# sc-7000z_supplyswitch.net
KiCad netlist of a schematic drawn in EAGLE
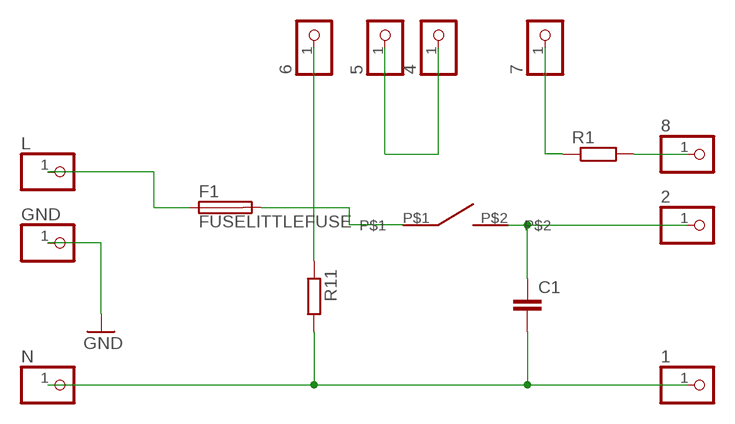
[diagram p0: schematic, sheet 1]

(export (version "E")
  (design (tool "Eeschema 10.0.6"))
  (components
    (comp (ref "1")
      (value "PINHD-1X1")
      (footprint "eagle-import:1X01")
      (libsource (lib "eagle-import") (part "PINHD-1X1"))
    )
    (comp (ref "2")
      (value "PINHD-1X1")
      (footprint "eagle-import:1X01")
      (libsource (lib "eagle-import") (part "PINHD-1X1"))
    )
    (comp (ref "4")
      (value "PINHD-1X1")
      (footprint "eagle-import:1X01")
      (libsource (lib "eagle-import") (part "PINHD-1X1"))
    )
    (comp (ref "5")
      (value "PINHD-1X1")
      (footprint "eagle-import:1X01")
      (libsource (lib "eagle-import") (part "PINHD-1X1"))
    )
    (comp (ref "6")
      (value "PINHD-1X1")
      (footprint "eagle-import:1X01")
      (libsource (lib "eagle-import") (part "PINHD-1X1"))
    )
    (comp (ref "7")
      (value "PINHD-1X1")
      (footprint "eagle-import:1X01")
      (libsource (lib "eagle-import") (part "PINHD-1X1"))
    )
    (comp (ref "8")
      (value "PINHD-1X1")
      (footprint "eagle-import:1X01")
      (libsource (lib "eagle-import") (part "PINHD-1X1"))
    )
    (comp (ref "C1")
      (value "C-EU150-054X183")
      (footprint "eagle-import:C150-054X183")
      (libsource (lib "eagle-import") (part "C-EU150-054X183"))
    )
    (comp (ref "F1")
      (value "FUSELITTLEFUSE")
      (footprint "eagle-import:LITTLEFUSE")
      (libsource (lib "eagle-import") (part "FUSELITTLEFUSE"))
    )
    (comp (ref "GND")
      (value "PINHD-1X1")
      (footprint "eagle-import:1X01")
      (libsource (lib "eagle-import") (part "PINHD-1X1"))
    )
    (comp (ref "L")
      (value "PINHD-1X1")
      (footprint "eagle-import:1X01")
      (libsource (lib "eagle-import") (part "PINHD-1X1"))
    )
    (comp (ref "N")
      (value "PINHD-1X1")
      (footprint "eagle-import:1X01")
      (libsource (lib "eagle-import") (part "PINHD-1X1"))
    )
    (comp (ref "R1")
      (value "R-EU_0309/12")
      (footprint "eagle-import:0309_12")
      (libsource (lib "eagle-import") (part "R-EU_0309/12"))
    )
    (comp (ref "R11")
      (value "R-EU_0309/12")
      (footprint "eagle-import:0309_12")
      (libsource (lib "eagle-import") (part "R-EU_0309/12"))
    )
    (comp (ref "U$1")
      (value "MY_SWITCH_ON_OFF")
      (footprint "eagle-import:KOLYSKA21X15")
      (libsource (lib "eagle-import") (part "MY_SWITCH_ON_OFF"))
    )
  )
  (nets
    (net (code "1") (name "GND") (class "Default")
      (node (ref "GND") (pin "1") (pinfunction "1_1") (pintype "passive"))
    )
    (net (code "2") (name "Net-(1-Pad1)") (class "Default")
      (node (ref "1") (pin "1") (pinfunction "1_1") (pintype "passive"))
      (node (ref "C1") (pin "2") (pinfunction "2_2") (pintype "passive"))
      (node (ref "N") (pin "1") (pinfunction "1_1") (pintype "passive"))
      (node (ref "R11") (pin "2") (pinfunction "2_2") (pintype "passive"))
    )
    (net (code "3") (name "Net-(2-Pad1)") (class "Default")
      (node (ref "2") (pin "1") (pinfunction "1_1") (pintype "passive"))
      (node (ref "C1") (pin "1") (pinfunction "1_1") (pintype "passive"))
      (node (ref "U$1") (pin "P$2") (pinfunction "P$2_P$2") (pintype "bidirectional"))
    )
    (net (code "4") (name "Net-(4-Pad1)") (class "Default")
      (node (ref "4") (pin "1") (pinfunction "1_1") (pintype "passive"))
      (node (ref "5") (pin "1") (pinfunction "1_1") (pintype "passive"))
    )
    (net (code "5") (name "Net-(6-Pad1)") (class "Default")
      (node (ref "6") (pin "1") (pinfunction "1_1") (pintype "passive"))
      (node (ref "R11") (pin "1") (pinfunction "1_1") (pintype "passive"))
    )
    (net (code "6") (name "Net-(7-Pad1)") (class "Default")
      (node (ref "7") (pin "1") (pinfunction "1_1") (pintype "passive"))
      (node (ref "R1") (pin "1") (pinfunction "1_1") (pintype "passive"))
    )
    (net (code "7") (name "Net-(8-Pad1)") (class "Default")
      (node (ref "8") (pin "1") (pinfunction "1_1") (pintype "passive"))
      (node (ref "R1") (pin "2") (pinfunction "2_2") (pintype "passive"))
    )
    (net (code "8") (name "Net-(F1-Pad1)") (class "Default")
      (node (ref "F1") (pin "1") (pinfunction "1_1") (pintype "passive"))
      (node (ref "L") (pin "1") (pinfunction "1_1") (pintype "passive"))
    )
    (net (code "9") (name "Net-(F1-Pad2)") (class "Default")
      (node (ref "F1") (pin "2") (pinfunction "2_2") (pintype "passive"))
      (node (ref "U$1") (pin "P$1") (pinfunction "P$1_P$1") (pintype "bidirectional"))
    )
  )
)
